# H_bridge_PFC161.net
KiCad netlist of a schematic drawn in Altium Designer
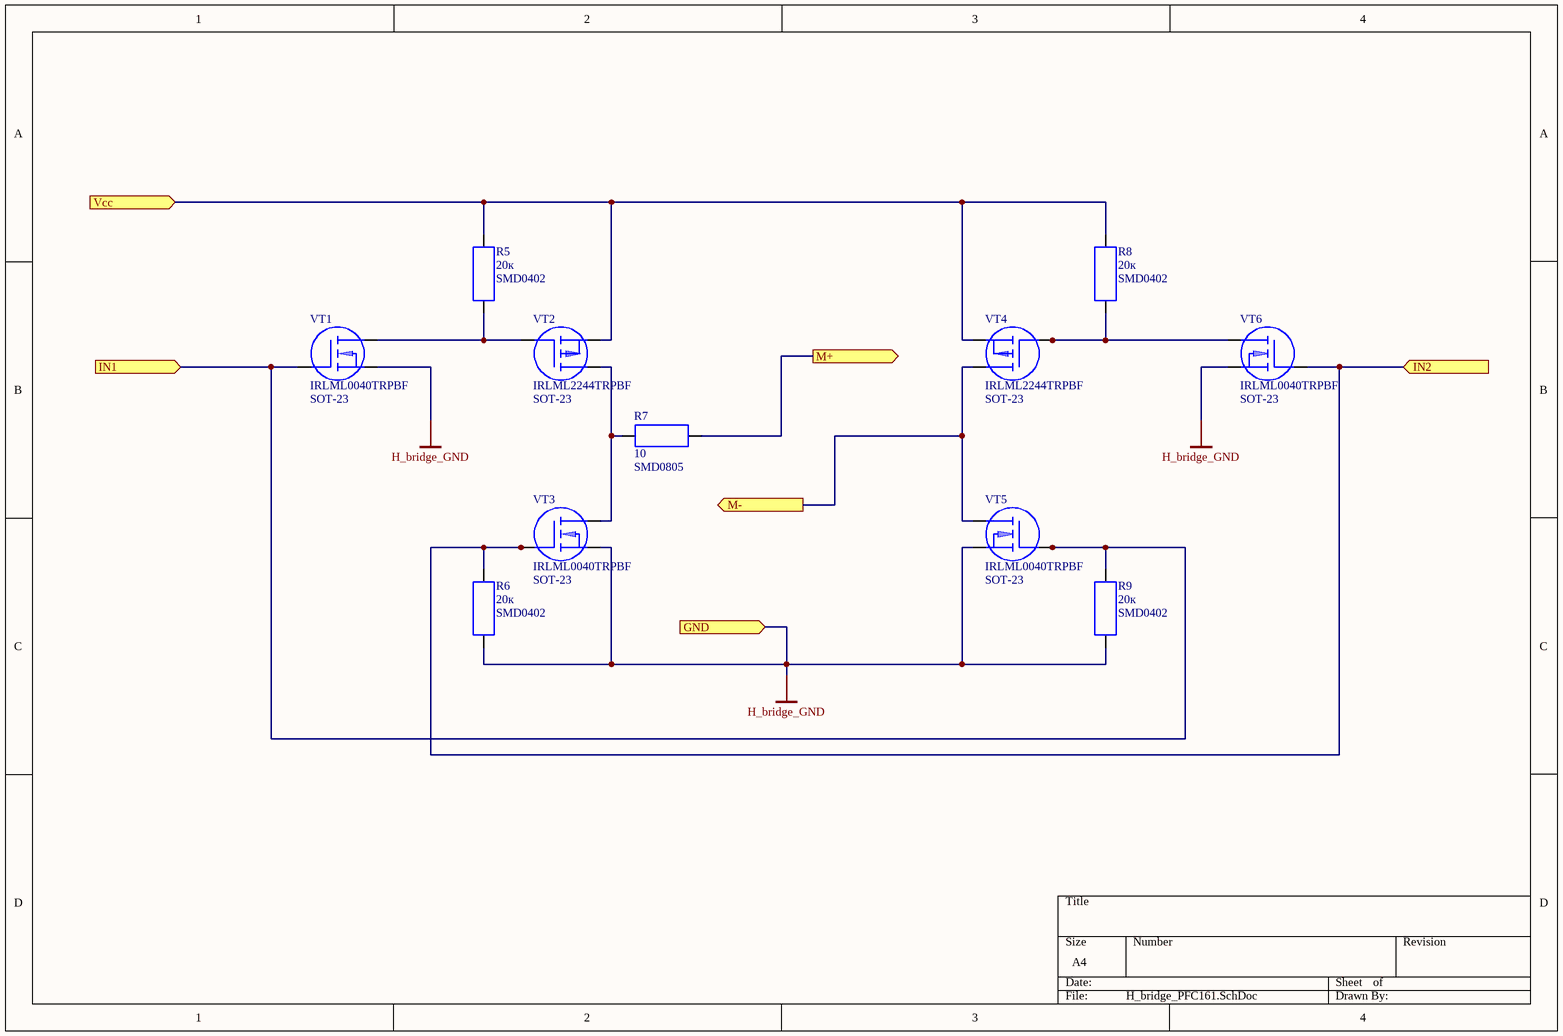
[diagram p0: H_bridge_PFC161.SchDoc]

(export (version "E")
  (design (tool "Eeschema 10.0.6"))
  (components
    (comp (ref "R5")
      (value "20к")
      (footprint "SMD0402(1608)")
      (fields (field (name "PACKAGE") "SMD0402"))
      (libsource (lib "MechanikLibrary") (part "R_0402"))
    )
    (comp (ref "R6")
      (value "20к")
      (footprint "SMD0402(1608)")
      (fields (field (name "PACKAGE") "SMD0402"))
      (libsource (lib "MechanikLibrary") (part "R_0402"))
    )
    (comp (ref "R7")
      (value "10")
      (footprint "SMD0805(2012)")
      (fields (field (name "PACKAGE") "SMD0805"))
      (libsource (lib "MechanikLibrary") (part "R_0805"))
    )
    (comp (ref "R8")
      (value "20к")
      (footprint "SMD0402(1608)")
      (fields (field (name "PACKAGE") "SMD0402"))
      (libsource (lib "MechanikLibrary") (part "R_0402"))
    )
    (comp (ref "R9")
      (value "20к")
      (footprint "SMD0402(1608)")
      (fields (field (name "PACKAGE") "SMD0402"))
      (libsource (lib "MechanikLibrary") (part "R_0402"))
    )
    (comp (ref "VT1")
      (value "IRLML0040TRPBF")
      (footprint "SOT23-3")
      (fields (field (name "PACKAGE") "SOT-23"))
      (libsource (lib "MechanikLibrary") (part "VT_N_MOSFET_SOT23_3"))
    )
    (comp (ref "VT2")
      (value "IRLML2244TRPBF")
      (footprint "SOT23-3")
      (fields (field (name "PACKAGE") "SOT-23"))
      (libsource (lib "MechanikLibrary") (part "VT_P_MOSFET_SOT23_3"))
    )
    (comp (ref "VT3")
      (value "IRLML0040TRPBF")
      (footprint "SOT23-3")
      (fields (field (name "PACKAGE") "SOT-23"))
      (libsource (lib "MechanikLibrary") (part "VT_N_MOSFET_SOT23_3"))
    )
    (comp (ref "VT4")
      (value "IRLML2244TRPBF")
      (footprint "SOT23-3")
      (fields (field (name "PACKAGE") "SOT-23"))
      (libsource (lib "MechanikLibrary") (part "VT_P_MOSFET_SOT23_3"))
    )
    (comp (ref "VT5")
      (value "IRLML0040TRPBF")
      (footprint "SOT23-3")
      (fields (field (name "PACKAGE") "SOT-23"))
      (libsource (lib "MechanikLibrary") (part "VT_N_MOSFET_SOT23_3"))
    )
    (comp (ref "VT6")
      (value "IRLML0040TRPBF")
      (footprint "SOT23-3")
      (fields (field (name "PACKAGE") "SOT-23"))
      (libsource (lib "MechanikLibrary") (part "VT_N_MOSFET_SOT23_3"))
    )
  )
  (nets
    (net (code "1") (name "/IN1") (class "Default")
      (node (ref "R9") (pin "1") (pintype "passive"))
      (node (ref "VT1") (pin "1") (pintype "passive"))
      (node (ref "VT5") (pin "1") (pintype "passive"))
    )
    (net (code "2") (name "/IN2") (class "Default")
      (node (ref "R6") (pin "1") (pintype "passive"))
      (node (ref "VT3") (pin "1") (pintype "passive"))
      (node (ref "VT6") (pin "1") (pintype "passive"))
    )
    (net (code "3") (name "/M+") (class "Default") (node (ref "R7") (pin "1") (pintype "passive")))
    (net (code "4") (name "/M-") (class "Default")
      (node (ref "VT4") (pin "3") (pintype "passive"))
      (node (ref "VT5") (pin "3") (pintype "passive"))
    )
    (net (code "5") (name "/Vcc") (class "Default")
      (node (ref "R5") (pin "1") (pintype "passive"))
      (node (ref "R8") (pin "1") (pintype "passive"))
      (node (ref "VT2") (pin "2") (pintype "passive"))
      (node (ref "VT4") (pin "2") (pintype "passive"))
    )
    (net (code "6") (name "H_bridge_GND") (class "Default")
      (node (ref "R6") (pin "2") (pintype "passive"))
      (node (ref "R9") (pin "2") (pintype "passive"))
      (node (ref "VT1") (pin "2") (pintype "passive"))
      (node (ref "VT3") (pin "2") (pintype "passive"))
      (node (ref "VT5") (pin "2") (pintype "passive"))
      (node (ref "VT6") (pin "2") (pintype "passive"))
    )
    (net (code "7") (name "Net-(R5-Pad2)") (class "Default")
      (node (ref "R5") (pin "2") (pintype "passive"))
      (node (ref "VT1") (pin "3") (pintype "passive"))
      (node (ref "VT2") (pin "1") (pintype "passive"))
    )
    (net (code "8") (name "Net-(R7-Pad2)") (class "Default")
      (node (ref "R7") (pin "2") (pintype "passive"))
      (node (ref "VT2") (pin "3") (pintype "passive"))
      (node (ref "VT3") (pin "3") (pintype "passive"))
    )
    (net (code "9") (name "Net-(R8-Pad2)") (class "Default")
      (node (ref "R8") (pin "2") (pintype "passive"))
      (node (ref "VT4") (pin "1") (pintype "passive"))
      (node (ref "VT6") (pin "3") (pintype "passive"))
    )
  )
)
